# SterownikCNC4_1.net
KiCad netlist of a schematic drawn in EAGLE
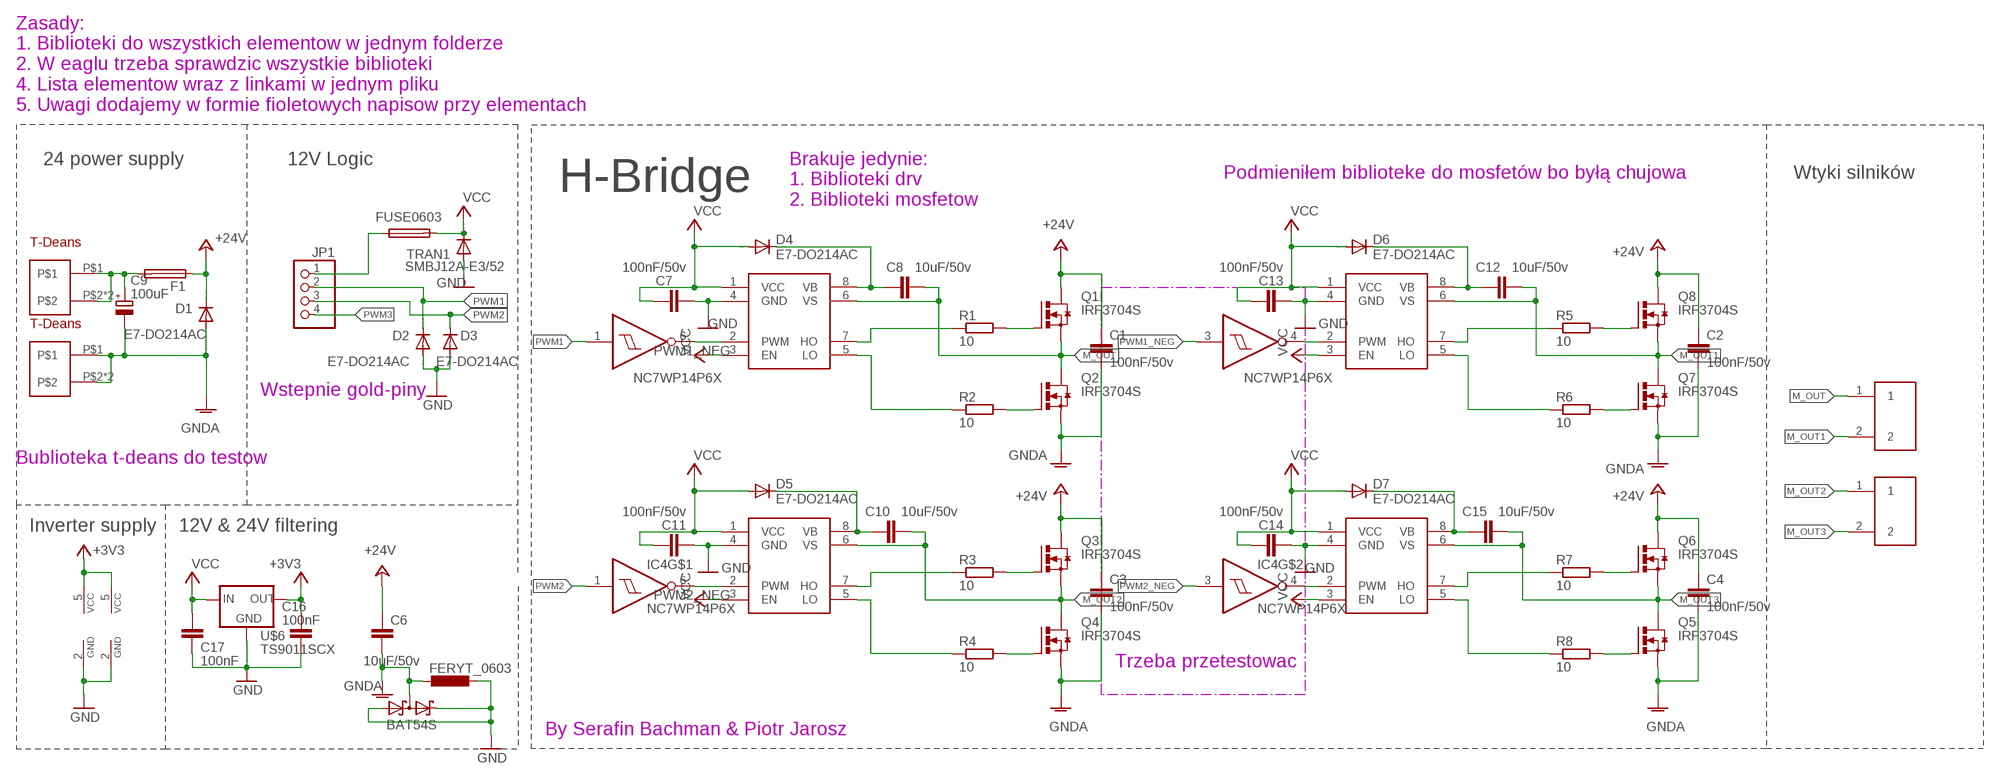
[diagram p0: schematic, sheet 1]

(export (version "E")
  (design (tool "Eeschema 10.0.6"))
  (components
    (comp (ref "C1")
      (value "100nF/50v")
      (footprint "eagle-import:C0603K")
      (libsource (lib "eagle-import") (part "C-EUC0603K"))
    )
    (comp (ref "C2")
      (value "100nF/50v")
      (footprint "eagle-import:C0603K")
      (libsource (lib "eagle-import") (part "C-EUC0603K"))
    )
    (comp (ref "C3")
      (value "100nF/50v")
      (footprint "eagle-import:C0603K")
      (libsource (lib "eagle-import") (part "C-EUC0603K"))
    )
    (comp (ref "C4")
      (value "100nF/50v")
      (footprint "eagle-import:C0603K")
      (libsource (lib "eagle-import") (part "C-EUC0603K"))
    )
    (comp (ref "C6")
      (value "10uF/50v")
      (footprint "eagle-import:C0603K")
      (libsource (lib "eagle-import") (part "C-EUC0603K"))
    )
    (comp (ref "C7")
      (value "100nF/50v")
      (footprint "eagle-import:C0603K")
      (libsource (lib "eagle-import") (part "C-EUC0603K"))
    )
    (comp (ref "C8")
      (value "10uF/50v")
      (footprint "eagle-import:C0603K")
      (libsource (lib "eagle-import") (part "C-EUC0603K"))
    )
    (comp (ref "C9")
      (value "100uF")
      (footprint "eagle-import:153CLV-0810")
      (libsource (lib "eagle-import") (part "CPOL-EU153CLV-0810"))
    )
    (comp (ref "C10")
      (value "10uF/50v")
      (footprint "eagle-import:C0603K")
      (libsource (lib "eagle-import") (part "C-EUC0603K"))
    )
    (comp (ref "C11")
      (value "100nF/50v")
      (footprint "eagle-import:C0603K")
      (libsource (lib "eagle-import") (part "C-EUC0603K"))
    )
    (comp (ref "C12")
      (value "10uF/50v")
      (footprint "eagle-import:C0603K")
      (libsource (lib "eagle-import") (part "C-EUC0603K"))
    )
    (comp (ref "C13")
      (value "100nF/50v")
      (footprint "eagle-import:C0603K")
      (libsource (lib "eagle-import") (part "C-EUC0603K"))
    )
    (comp (ref "C14")
      (value "100nF/50v")
      (footprint "eagle-import:C0603K")
      (libsource (lib "eagle-import") (part "C-EUC0603K"))
    )
    (comp (ref "C15")
      (value "10uF/50v")
      (footprint "eagle-import:C0603K")
      (libsource (lib "eagle-import") (part "C-EUC0603K"))
    )
    (comp (ref "C16")
      (value "100nF")
      (footprint "eagle-import:C0603K")
      (libsource (lib "eagle-import") (part "C-EUC0603K"))
    )
    (comp (ref "C17")
      (value "100nF")
      (footprint "eagle-import:C0603K")
      (libsource (lib "eagle-import") (part "C-EUC0603K"))
    )
    (comp (ref "D1")
      (value "E7-DO214AC")
      (footprint "eagle-import:DO214AC")
      (libsource (lib "eagle-import") (part "E7-DO214AC"))
    )
    (comp (ref "D2")
      (value "E7-DO214AC")
      (footprint "eagle-import:DO214AC")
      (libsource (lib "eagle-import") (part "E7-DO214AC"))
    )
    (comp (ref "D3")
      (value "E7-DO214AC")
      (footprint "eagle-import:DO214AC")
      (libsource (lib "eagle-import") (part "E7-DO214AC"))
    )
    (comp (ref "D4")
      (value "E7-DO214AC")
      (footprint "eagle-import:DO214AC")
      (libsource (lib "eagle-import") (part "E7-DO214AC"))
    )
    (comp (ref "D5")
      (value "E7-DO214AC")
      (footprint "eagle-import:DO214AC")
      (libsource (lib "eagle-import") (part "E7-DO214AC"))
    )
    (comp (ref "D6")
      (value "E7-DO214AC")
      (footprint "eagle-import:DO214AC")
      (libsource (lib "eagle-import") (part "E7-DO214AC"))
    )
    (comp (ref "D7")
      (value "E7-DO214AC")
      (footprint "eagle-import:DO214AC")
      (libsource (lib "eagle-import") (part "E7-DO214AC"))
    )
    (comp (ref "D8")
      (value "BAT54S")
      (footprint "eagle-import:SOT23")
      (libsource (lib "eagle-import") (part "BAT54S"))
    )
    (comp (ref "F1")
      (value "TE5")
      (footprint "eagle-import:TE5")
      (libsource (lib "eagle-import") (part "TE5"))
    )
    (comp (ref "IC1")
      (value "NC7WP14P6X")
      (footprint "eagle-import:SOT65P210X110-6AN_SC88_SC70-6")
      (libsource (lib "eagle-import") (part "NC7W14P6XP"))
    )
    (comp (ref "IC4")
      (value "NC7WP14P6X")
      (footprint "eagle-import:SOT65P210X110-6AN_SC88_SC70-6")
      (libsource (lib "eagle-import") (part "NC7W14P6XP"))
    )
    (comp (ref "JP1")
      (value "PINHD-1X4")
      (footprint "eagle-import:1X04")
      (libsource (lib "eagle-import") (part "PINHD-1X4"))
    )
    (comp (ref "Q1")
      (value "IRF3704S")
      (footprint "eagle-import:D2PACK")
      (libsource (lib "eagle-import") (part "IRF3704S"))
    )
    (comp (ref "Q2")
      (value "IRF3704S")
      (footprint "eagle-import:D2PACK")
      (libsource (lib "eagle-import") (part "IRF3704S"))
    )
    (comp (ref "Q3")
      (value "IRF3704S")
      (footprint "eagle-import:D2PACK")
      (libsource (lib "eagle-import") (part "IRF3704S"))
    )
    (comp (ref "Q4")
      (value "IRF3704S")
      (footprint "eagle-import:D2PACK")
      (libsource (lib "eagle-import") (part "IRF3704S"))
    )
    (comp (ref "Q5")
      (value "IRF3704S")
      (footprint "eagle-import:D2PACK")
      (libsource (lib "eagle-import") (part "IRF3704S"))
    )
    (comp (ref "Q6")
      (value "IRF3704S")
      (footprint "eagle-import:D2PACK")
      (libsource (lib "eagle-import") (part "IRF3704S"))
    )
    (comp (ref "Q7")
      (value "IRF3704S")
      (footprint "eagle-import:D2PACK")
      (libsource (lib "eagle-import") (part "IRF3704S"))
    )
    (comp (ref "Q8")
      (value "IRF3704S")
      (footprint "eagle-import:D2PACK")
      (libsource (lib "eagle-import") (part "IRF3704S"))
    )
    (comp (ref "R1")
      (value "10")
      (footprint "eagle-import:R0603")
      (libsource (lib "eagle-import") (part "R-EU_R0603"))
    )
    (comp (ref "R2")
      (value "10")
      (footprint "eagle-import:R0603")
      (libsource (lib "eagle-import") (part "R-EU_R0603"))
    )
    (comp (ref "R3")
      (value "10")
      (footprint "eagle-import:R0603")
      (libsource (lib "eagle-import") (part "R-EU_R0603"))
    )
    (comp (ref "R4")
      (value "10")
      (footprint "eagle-import:R0603")
      (libsource (lib "eagle-import") (part "R-EU_R0603"))
    )
    (comp (ref "R5")
      (value "10")
      (footprint "eagle-import:R0603")
      (libsource (lib "eagle-import") (part "R-EU_R0603"))
    )
    (comp (ref "R6")
      (value "10")
      (footprint "eagle-import:R0603")
      (libsource (lib "eagle-import") (part "R-EU_R0603"))
    )
    (comp (ref "R7")
      (value "10")
      (footprint "eagle-import:R0603")
      (libsource (lib "eagle-import") (part "R-EU_R0603"))
    )
    (comp (ref "R8")
      (value "10")
      (footprint "eagle-import:R0603")
      (libsource (lib "eagle-import") (part "R-EU_R0603"))
    )
    (comp (ref "TRAN1")
      (value "SMBJ12A-E3/52")
      (footprint "eagle-import:DO214AA")
      (libsource (lib "eagle-import") (part "SMBJ12A-E3/52"))
    )
    (comp (ref "U$2")
      (value "T-DEANS")
      (footprint "eagle-import:T-DEANS")
      (libsource (lib "eagle-import") (part "T-DEANS"))
    )
    (comp (ref "U$3")
      (value "FUSE0603")
      (footprint "eagle-import:0603")
      (libsource (lib "eagle-import") (part "FUSE0603"))
    )
    (comp (ref "U$4")
      (value "FERYT_0603")
      (footprint "eagle-import:R0603")
      (libsource (lib "eagle-import") (part "FERYT_0603"))
    )
    (comp (ref "U$5")
      (value "T-DEANS")
      (footprint "eagle-import:T-DEANS")
      (libsource (lib "eagle-import") (part "T-DEANS"))
    )
    (comp (ref "U$6")
      (value "TS9011SCX")
      (footprint "eagle-import:SOT23")
      (libsource (lib "eagle-import") (part "TS9011SCX"))
    )
    (comp (ref "U$7")
      (value "PTB-02_5.08MM")
      (footprint "eagle-import:PTB-5.08MM-02")
      (libsource (lib "eagle-import") (part "PTB-02_5.08MM"))
    )
    (comp (ref "U$9")
      (value "PTB-02_5.08MM")
      (footprint "eagle-import:PTB-5.08MM-02")
      (libsource (lib "eagle-import") (part "PTB-02_5.08MM"))
    )
    (comp (ref "U1")
      (value "IR2104")
      (footprint "eagle-import:SO08")
      (libsource (lib "eagle-import") (part "IR2104"))
    )
    (comp (ref "U2")
      (value "IR2104")
      (footprint "eagle-import:SO08")
      (libsource (lib "eagle-import") (part "IR2104"))
    )
    (comp (ref "U3")
      (value "IR2104")
      (footprint "eagle-import:SO08")
      (libsource (lib "eagle-import") (part "IR2104"))
    )
    (comp (ref "U4")
      (value "IR2104")
      (footprint "eagle-import:SO08")
      (libsource (lib "eagle-import") (part "IR2104"))
    )
  )
  (nets
    (net (code "1") (name "+3V3") (class "Default")
      (node (ref "C16") (pin "1") (pinfunction "1_1") (pintype "passive"))
      (node (ref "IC1") (pin "5") (pinfunction "VCC_5") (pintype "power_in"))
      (node (ref "IC4") (pin "5") (pinfunction "VCC_5") (pintype "power_in"))
      (node (ref "U$6") (pin "2") (pinfunction "OUT_2") (pintype "passive"))
    )
    (net (code "2") (name "+24V") (class "Default")
      (node (ref "C1") (pin "1") (pinfunction "1_1") (pintype "passive"))
      (node (ref "C2") (pin "1") (pinfunction "1_1") (pintype "passive"))
      (node (ref "C3") (pin "1") (pinfunction "1_1") (pintype "passive"))
      (node (ref "C4") (pin "1") (pinfunction "1_1") (pintype "passive"))
      (node (ref "C6") (pin "1") (pinfunction "1_1") (pintype "passive"))
      (node (ref "D1") (pin "C") (pinfunction "C_C") (pintype "passive"))
      (node (ref "F1") (pin "1") (pinfunction "1_1") (pintype "passive"))
      (node (ref "Q1") (pin "2") (pinfunction "D_2") (pintype "passive"))
      (node (ref "Q3") (pin "2") (pinfunction "D_2") (pintype "passive"))
      (node (ref "Q6") (pin "2") (pinfunction "D_2") (pintype "passive"))
      (node (ref "Q8") (pin "2") (pinfunction "D_2") (pintype "passive"))
    )
    (net (code "3") (name "GND") (class "Default")
      (node (ref "C11") (pin "2") (pinfunction "2_2") (pintype "passive"))
      (node (ref "C13") (pin "2") (pinfunction "2_2") (pintype "passive"))
      (node (ref "C14") (pin "2") (pinfunction "2_2") (pintype "passive"))
      (node (ref "C16") (pin "2") (pinfunction "2_2") (pintype "passive"))
      (node (ref "C17") (pin "2") (pinfunction "2_2") (pintype "passive"))
      (node (ref "C7") (pin "2") (pinfunction "2_2") (pintype "passive"))
      (node (ref "D2") (pin "A") (pinfunction "A_A") (pintype "passive"))
      (node (ref "D3") (pin "A") (pinfunction "A_A") (pintype "passive"))
      (node (ref "D8") (pin "1") (pinfunction "A1_1") (pintype "passive"))
      (node (ref "D8") (pin "2") (pinfunction "C2_2") (pintype "passive"))
      (node (ref "IC1") (pin "2") (pinfunction "GND_2") (pintype "power_in"))
      (node (ref "IC4") (pin "2") (pinfunction "GND_2") (pintype "power_in"))
      (node (ref "TRAN1") (pin "A") (pinfunction "A_A") (pintype "passive"))
      (node (ref "U$4") (pin "2") (pinfunction "2_2") (pintype "passive"))
      (node (ref "U$6") (pin "1") (pinfunction "GND_1") (pintype "input"))
      (node (ref "U1") (pin "4") (pinfunction "GND_4") (pintype "passive"))
      (node (ref "U2") (pin "4") (pinfunction "GND_4") (pintype "passive"))
      (node (ref "U3") (pin "4") (pinfunction "GND_4") (pintype "passive"))
      (node (ref "U4") (pin "4") (pinfunction "GND_4") (pintype "passive"))
    )
    (net (code "4") (name "GNDA") (class "Default")
      (node (ref "C1") (pin "2") (pinfunction "2_2") (pintype "passive"))
      (node (ref "C2") (pin "2") (pinfunction "2_2") (pintype "passive"))
      (node (ref "C3") (pin "2") (pinfunction "2_2") (pintype "passive"))
      (node (ref "C4") (pin "2") (pinfunction "2_2") (pintype "passive"))
      (node (ref "C6") (pin "2") (pinfunction "2_2") (pintype "passive"))
      (node (ref "C9") (pin "-") (pinfunction "-_-") (pintype "passive"))
      (node (ref "D1") (pin "A") (pinfunction "A_A") (pintype "passive"))
      (node (ref "D8") (pin "3") (pinfunction "C1A2_3") (pintype "passive"))
      (node (ref "Q2") (pin "3") (pinfunction "S_3") (pintype "passive"))
      (node (ref "Q4") (pin "3") (pinfunction "S_3") (pintype "passive"))
      (node (ref "Q5") (pin "3") (pinfunction "S_3") (pintype "passive"))
      (node (ref "Q7") (pin "3") (pinfunction "S_3") (pintype "passive"))
      (node (ref "U$4") (pin "1") (pinfunction "1_1") (pintype "passive"))
      (node (ref "U$5") (pin "P$1") (pinfunction "P$1_P$1") (pintype "bidirectional"))
      (node (ref "U$5") (pin "P$2") (pinfunction "P$2_P$2") (pintype "bidirectional"))
      (node (ref "U$5") (pin "P$3") (pinfunction "P$2_P$3") (pintype "bidirectional"))
    )
    (net (code "5") (name "M_OUT") (class "Default")
      (node (ref "C8") (pin "2") (pinfunction "2_2") (pintype "passive"))
      (node (ref "Q1") (pin "3") (pinfunction "S_3") (pintype "passive"))
      (node (ref "Q2") (pin "2") (pinfunction "D_2") (pintype "passive"))
      (node (ref "U$7") (pin "1") (pinfunction "1_1") (pintype "bidirectional"))
      (node (ref "U1") (pin "6") (pinfunction "VS_6") (pintype "passive"))
    )
    (net (code "6") (name "M_OUT1") (class "Default")
      (node (ref "C12") (pin "2") (pinfunction "2_2") (pintype "passive"))
      (node (ref "Q7") (pin "2") (pinfunction "D_2") (pintype "passive"))
      (node (ref "Q8") (pin "3") (pinfunction "S_3") (pintype "passive"))
      (node (ref "U$7") (pin "2") (pinfunction "2_2") (pintype "bidirectional"))
      (node (ref "U2") (pin "6") (pinfunction "VS_6") (pintype "passive"))
    )
    (net (code "7") (name "M_OUT2") (class "Default")
      (node (ref "C10") (pin "2") (pinfunction "2_2") (pintype "passive"))
      (node (ref "Q3") (pin "3") (pinfunction "S_3") (pintype "passive"))
      (node (ref "Q4") (pin "2") (pinfunction "D_2") (pintype "passive"))
      (node (ref "U$9") (pin "1") (pinfunction "1_1") (pintype "bidirectional"))
      (node (ref "U3") (pin "6") (pinfunction "VS_6") (pintype "passive"))
    )
    (net (code "8") (name "M_OUT3") (class "Default")
      (node (ref "C15") (pin "2") (pinfunction "2_2") (pintype "passive"))
      (node (ref "Q5") (pin "2") (pinfunction "D_2") (pintype "passive"))
      (node (ref "Q6") (pin "3") (pinfunction "S_3") (pintype "passive"))
      (node (ref "U$9") (pin "2") (pinfunction "2_2") (pintype "bidirectional"))
      (node (ref "U4") (pin "6") (pinfunction "VS_6") (pintype "passive"))
    )
    (net (code "9") (name "Net-(C9-Pad+)") (class "Default")
      (node (ref "C9") (pin "+") (pinfunction "+_+") (pintype "passive"))
      (node (ref "F1") (pin "2") (pinfunction "2_2") (pintype "passive"))
      (node (ref "U$2") (pin "P$1") (pinfunction "P$1_P$1") (pintype "bidirectional"))
      (node (ref "U$2") (pin "P$2") (pinfunction "P$2_P$2") (pintype "bidirectional"))
      (node (ref "U$2") (pin "P$3") (pinfunction "P$2_P$3") (pintype "bidirectional"))
    )
    (net (code "10") (name "Net-(IC1B-O)") (class "Default")
      (node (ref "IC1") (pin "4") (pinfunction "O_4") (pintype "output"))
      (node (ref "U2") (pin "2") (pinfunction "PWM_2") (pintype "input"))
    )
    (net (code "11") (name "Net-(IC4B-O)") (class "Default")
      (node (ref "IC4") (pin "4") (pinfunction "O_4") (pintype "output"))
      (node (ref "U4") (pin "2") (pinfunction "PWM_2") (pintype "input"))
    )
    (net (code "12") (name "Net-(JP1-Pad1)") (class "Default")
      (node (ref "JP1") (pin "1") (pinfunction "1_1") (pintype "passive"))
      (node (ref "U$3") (pin "1") (pinfunction "1_1") (pintype "passive"))
    )
    (net (code "13") (name "Net-(Q1-G)") (class "Default")
      (node (ref "Q1") (pin "1") (pinfunction "G_1") (pintype "passive"))
      (node (ref "R1") (pin "2") (pinfunction "2_2") (pintype "passive"))
    )
    (net (code "14") (name "Net-(Q2-G)") (class "Default")
      (node (ref "Q2") (pin "1") (pinfunction "G_1") (pintype "passive"))
      (node (ref "R2") (pin "2") (pinfunction "2_2") (pintype "passive"))
    )
    (net (code "15") (name "Net-(Q3-G)") (class "Default")
      (node (ref "Q3") (pin "1") (pinfunction "G_1") (pintype "passive"))
      (node (ref "R3") (pin "2") (pinfunction "2_2") (pintype "passive"))
    )
    (net (code "16") (name "Net-(Q4-G)") (class "Default")
      (node (ref "Q4") (pin "1") (pinfunction "G_1") (pintype "passive"))
      (node (ref "R4") (pin "2") (pinfunction "2_2") (pintype "passive"))
    )
    (net (code "17") (name "Net-(Q5-G)") (class "Default")
      (node (ref "Q5") (pin "1") (pinfunction "G_1") (pintype "passive"))
      (node (ref "R8") (pin "2") (pinfunction "2_2") (pintype "passive"))
    )
    (net (code "18") (name "Net-(Q6-G)") (class "Default")
      (node (ref "Q6") (pin "1") (pinfunction "G_1") (pintype "passive"))
      (node (ref "R7") (pin "2") (pinfunction "2_2") (pintype "passive"))
    )
    (net (code "19") (name "Net-(Q7-G)") (class "Default")
      (node (ref "Q7") (pin "1") (pinfunction "G_1") (pintype "passive"))
      (node (ref "R6") (pin "2") (pinfunction "2_2") (pintype "passive"))
    )
    (net (code "20") (name "Net-(Q8-G)") (class "Default")
      (node (ref "Q8") (pin "1") (pinfunction "G_1") (pintype "passive"))
      (node (ref "R5") (pin "2") (pinfunction "2_2") (pintype "passive"))
    )
    (net (code "21") (name "Net-(U1-HO)") (class "Default")
      (node (ref "R1") (pin "1") (pinfunction "1_1") (pintype "passive"))
      (node (ref "U1") (pin "7") (pinfunction "HO_7") (pintype "output"))
    )
    (net (code "22") (name "Net-(U1-LO)") (class "Default")
      (node (ref "R2") (pin "1") (pinfunction "1_1") (pintype "passive"))
      (node (ref "U1") (pin "5") (pinfunction "LO_5") (pintype "output"))
    )
    (net (code "23") (name "Net-(U1-VB)") (class "Default")
      (node (ref "C8") (pin "1") (pinfunction "1_1") (pintype "passive"))
      (node (ref "D4") (pin "C") (pinfunction "C_C") (pintype "passive"))
      (node (ref "U1") (pin "8") (pinfunction "VB_8") (pintype "passive"))
    )
    (net (code "24") (name "Net-(U2-HO)") (class "Default")
      (node (ref "R5") (pin "1") (pinfunction "1_1") (pintype "passive"))
      (node (ref "U2") (pin "7") (pinfunction "HO_7") (pintype "output"))
    )
    (net (code "25") (name "Net-(U2-LO)") (class "Default")
      (node (ref "R6") (pin "1") (pinfunction "1_1") (pintype "passive"))
      (node (ref "U2") (pin "5") (pinfunction "LO_5") (pintype "output"))
    )
    (net (code "26") (name "Net-(U2-VB)") (class "Default")
      (node (ref "C12") (pin "1") (pinfunction "1_1") (pintype "passive"))
      (node (ref "D6") (pin "C") (pinfunction "C_C") (pintype "passive"))
      (node (ref "U2") (pin "8") (pinfunction "VB_8") (pintype "passive"))
    )
    (net (code "27") (name "Net-(U3-HO)") (class "Default")
      (node (ref "R3") (pin "1") (pinfunction "1_1") (pintype "passive"))
      (node (ref "U3") (pin "7") (pinfunction "HO_7") (pintype "output"))
    )
    (net (code "28") (name "Net-(U3-LO)") (class "Default")
      (node (ref "R4") (pin "1") (pinfunction "1_1") (pintype "passive"))
      (node (ref "U3") (pin "5") (pinfunction "LO_5") (pintype "output"))
    )
    (net (code "29") (name "Net-(U3-VB)") (class "Default")
      (node (ref "C10") (pin "1") (pinfunction "1_1") (pintype "passive"))
      (node (ref "D5") (pin "C") (pinfunction "C_C") (pintype "passive"))
      (node (ref "U3") (pin "8") (pinfunction "VB_8") (pintype "passive"))
    )
    (net (code "30") (name "Net-(U4-HO)") (class "Default")
      (node (ref "R7") (pin "1") (pinfunction "1_1") (pintype "passive"))
      (node (ref "U4") (pin "7") (pinfunction "HO_7") (pintype "output"))
    )
    (net (code "31") (name "Net-(U4-LO)") (class "Default")
      (node (ref "R8") (pin "1") (pinfunction "1_1") (pintype "passive"))
      (node (ref "U4") (pin "5") (pinfunction "LO_5") (pintype "output"))
    )
    (net (code "32") (name "Net-(U4-VB)") (class "Default")
      (node (ref "C15") (pin "1") (pinfunction "1_1") (pintype "passive"))
      (node (ref "D7") (pin "C") (pinfunction "C_C") (pintype "passive"))
      (node (ref "U4") (pin "8") (pinfunction "VB_8") (pintype "passive"))
    )
    (net (code "33") (name "PWM1") (class "Default")
      (node (ref "D2") (pin "C") (pinfunction "C_C") (pintype "passive"))
      (node (ref "IC1") (pin "1") (pinfunction "I_1") (pintype "input"))
      (node (ref "JP1") (pin "2") (pinfunction "2_2") (pintype "passive"))
    )
    (net (code "34") (name "PWM1_NEG") (class "Default")
      (node (ref "IC1") (pin "3") (pinfunction "I_3") (pintype "input"))
      (node (ref "IC1") (pin "6") (pinfunction "O_6") (pintype "output"))
      (node (ref "U1") (pin "2") (pinfunction "PWM_2") (pintype "input"))
    )
    (net (code "35") (name "PWM2") (class "Default")
      (node (ref "D3") (pin "C") (pinfunction "C_C") (pintype "passive"))
      (node (ref "IC4") (pin "1") (pinfunction "I_1") (pintype "input"))
      (node (ref "JP1") (pin "3") (pinfunction "3_3") (pintype "passive"))
    )
    (net (code "36") (name "PWM2_NEG") (class "Default")
      (node (ref "IC4") (pin "3") (pinfunction "I_3") (pintype "input"))
      (node (ref "IC4") (pin "6") (pinfunction "O_6") (pintype "output"))
      (node (ref "U3") (pin "2") (pinfunction "PWM_2") (pintype "input"))
    )
    (net (code "37") (name "PWM3") (class "Default")
      (node (ref "JP1") (pin "4") (pinfunction "4_4") (pintype "passive"))
    )
    (net (code "38") (name "VCC") (class "Default")
      (node (ref "C11") (pin "1") (pinfunction "1_1") (pintype "passive"))
      (node (ref "C13") (pin "1") (pinfunction "1_1") (pintype "passive"))
      (node (ref "C14") (pin "1") (pinfunction "1_1") (pintype "passive"))
      (node (ref "C17") (pin "1") (pinfunction "1_1") (pintype "passive"))
      (node (ref "C7") (pin "1") (pinfunction "1_1") (pintype "passive"))
      (node (ref "D4") (pin "A") (pinfunction "A_A") (pintype "passive"))
      (node (ref "D5") (pin "A") (pinfunction "A_A") (pintype "passive"))
      (node (ref "D6") (pin "A") (pinfunction "A_A") (pintype "passive"))
      (node (ref "D7") (pin "A") (pinfunction "A_A") (pintype "passive"))
      (node (ref "TRAN1") (pin "C") (pinfunction "C_C") (pintype "passive"))
      (node (ref "U$3") (pin "2") (pinfunction "2_2") (pintype "passive"))
      (node (ref "U$6") (pin "3") (pinfunction "IN_3") (pintype "input"))
      (node (ref "U1") (pin "1") (pinfunction "VCC_1") (pintype "passive"))
      (node (ref "U1") (pin "3") (pinfunction "EN_3") (pintype "input"))
      (node (ref "U2") (pin "1") (pinfunction "VCC_1") (pintype "passive"))
      (node (ref "U2") (pin "3") (pinfunction "EN_3") (pintype "input"))
      (node (ref "U3") (pin "1") (pinfunction "VCC_1") (pintype "passive"))
      (node (ref "U3") (pin "3") (pinfunction "EN_3") (pintype "input"))
      (node (ref "U4") (pin "1") (pinfunction "VCC_1") (pintype "passive"))
      (node (ref "U4") (pin "3") (pinfunction "EN_3") (pintype "input"))
    )
  )
)
